# charging_booster.net
KiCad netlist of a schematic drawn in Altium Designer
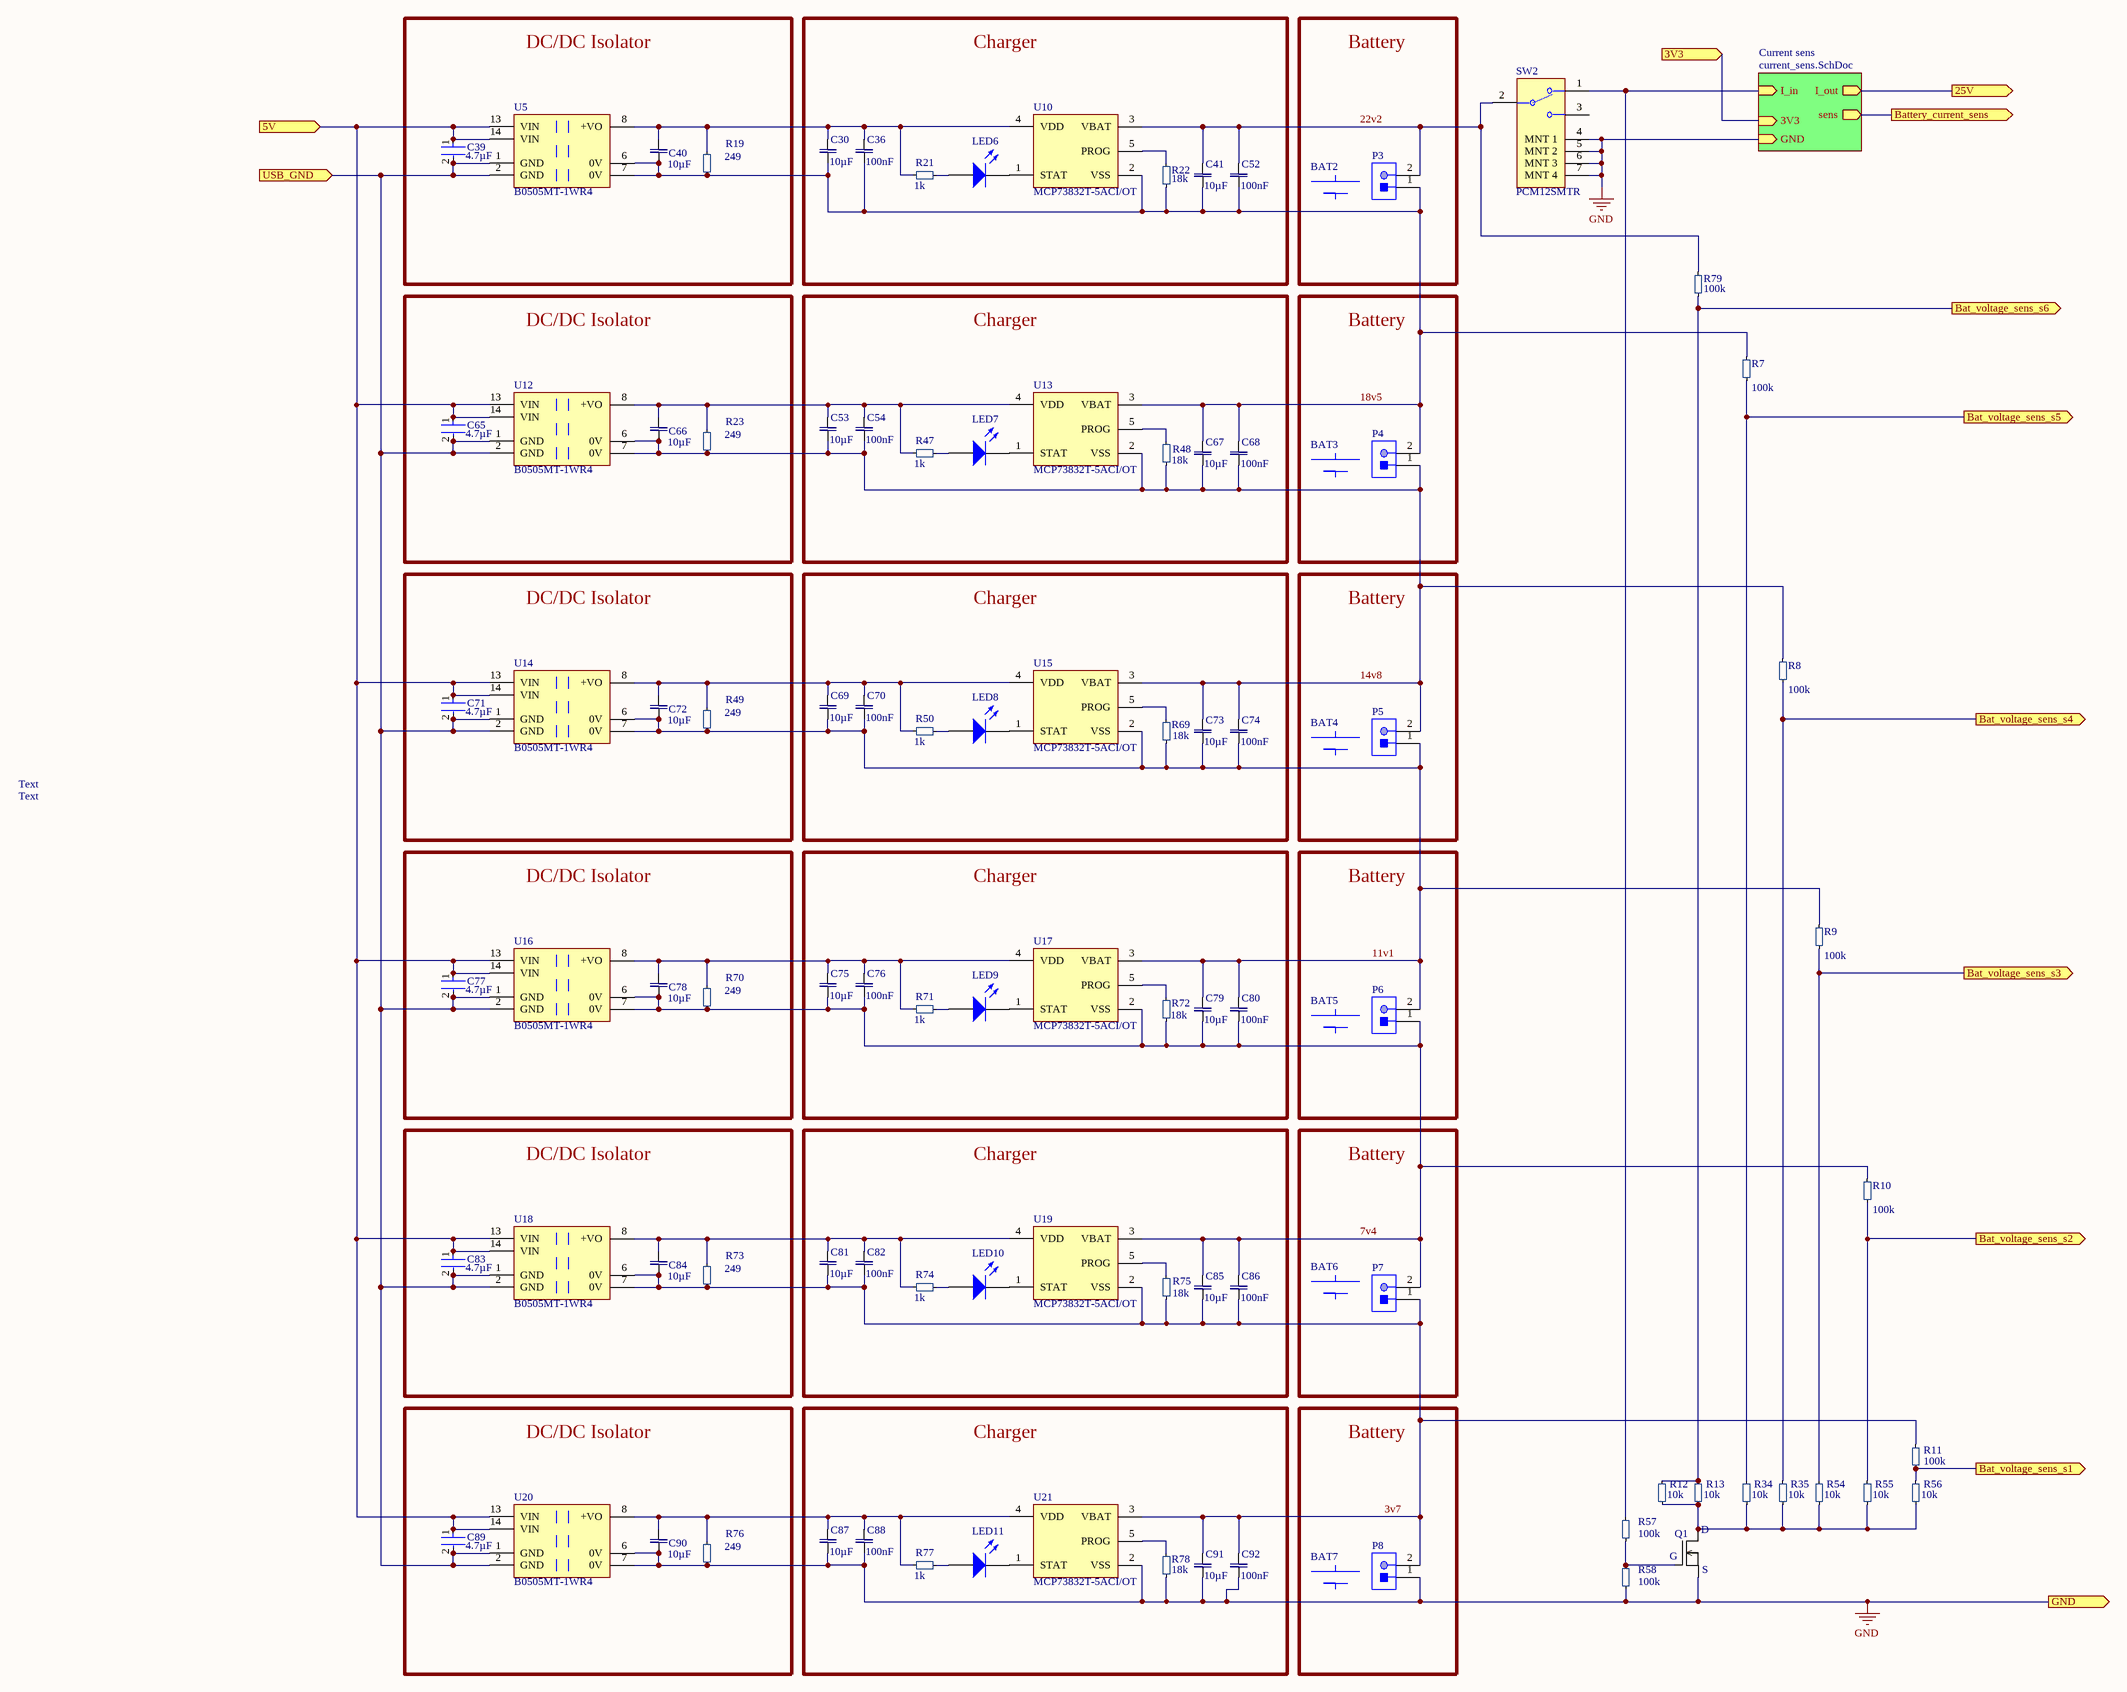
[diagram p0: charging_booster.SchDoc]

(export (version "E")
  (design (tool "Eeschema 10.0.6"))
  (components
    (comp (ref "BAT2")
      (value "702035_380mAH_20C_ebay")
      (description "https://www.ebay.com/itm/122071978357")
      (fields (field (name "VOLTAGE") "3.7V"))
      (libsource (lib "concord server") (part "606090_4000mAH_ebay"))
    )
    (comp (ref "BAT3")
      (value "702035_380mAH_20C_ebay")
      (description "https://www.ebay.com/itm/122071978357")
      (fields (field (name "VOLTAGE") "3.7V"))
      (libsource (lib "concord server") (part "606090_4000mAH_ebay"))
    )
    (comp (ref "BAT4")
      (value "702035_380mAH_20C_ebay")
      (description "https://www.ebay.com/itm/122071978357")
      (fields (field (name "VOLTAGE") "3.7V"))
      (libsource (lib "concord server") (part "606090_4000mAH_ebay"))
    )
    (comp (ref "BAT5")
      (value "702035_380mAH_20C_ebay")
      (description "https://www.ebay.com/itm/122071978357")
      (fields (field (name "VOLTAGE") "3.7V"))
      (libsource (lib "concord server") (part "606090_4000mAH_ebay"))
    )
    (comp (ref "BAT6")
      (value "702035_380mAH_20C_ebay")
      (description "https://www.ebay.com/itm/122071978357")
      (fields (field (name "VOLTAGE") "3.7V"))
      (libsource (lib "concord server") (part "606090_4000mAH_ebay"))
    )
    (comp (ref "BAT7")
      (value "702035_380mAH_20C_ebay")
      (description "https://www.ebay.com/itm/122071978357")
      (fields (field (name "VOLTAGE") "3.7V"))
      (libsource (lib "concord server") (part "606090_4000mAH_ebay"))
    )
    (comp (ref "C30")
      (value "CL31A106MBHNNNE")
      (footprint "Chip2PinSM127P600-8N")
      (description "CAP CER 10UF 50V X5R 1206")
      (fields (field (name "CAPACITANCE") "10µF") (field (name "TOLERANCE") "20%"))
      (libsource (lib "concord server") (part "Capasitor_keramic_generic"))
    )
    (comp (ref "C36")
      (value "GRM155R71H104ME14D")
      (footprint "cap0402")
      (description "0402 0.1 uF 50 V ±20% Tolerance X7R SMT Monolithic Ceramic Chip Capacitor")
      (fields (field (name "CAPACITANCE") "100nF") (field (name "TOLERANCE") "20%"))
      (libsource (lib "concord server") (part "Capasitor_keramic_generic"))
    )
    (comp (ref "C39")
      (value "CL21A475KAQNNNE")
      (footprint "FP-CL21-IPC_A")
      (fields (field (name "CAPACITANCE") "4.7µF") (field (name "TOLERANCE") "10%"))
      (libsource (lib "concord server") (part "b4654b650e69147ec39a6b967a45e02"))
    )
    (comp (ref "C40")
      (value "CL31A106MBHNNNE")
      (footprint "Chip2PinSM127P600-8N")
      (description "CAP CER 10UF 50V X5R 1206")
      (fields (field (name "CAPACITANCE") "10µF") (field (name "TOLERANCE") "20%"))
      (libsource (lib "concord server") (part "Capasitor_keramic_generic"))
    )
    (comp (ref "C41")
      (value "CL31A106MBHNNNE")
      (footprint "Chip2PinSM127P600-8N")
      (description "CAP CER 10UF 50V X5R 1206")
      (fields (field (name "CAPACITANCE") "10µF") (field (name "TOLERANCE") "20%"))
      (libsource (lib "concord server") (part "Capasitor_keramic_generic"))
    )
    (comp (ref "C52")
      (value "GRM155R71H104ME14D")
      (footprint "cap0402")
      (description "0402 0.1 uF 50 V ±20% Tolerance X7R SMT Monolithic Ceramic Chip Capacitor")
      (fields (field (name "CAPACITANCE") "100nF") (field (name "TOLERANCE") "20%"))
      (libsource (lib "concord server") (part "Capasitor_keramic_generic"))
    )
    (comp (ref "C53")
      (value "CL31A106MBHNNNE")
      (footprint "Chip2PinSM127P600-8N")
      (description "CAP CER 10UF 50V X5R 1206")
      (fields (field (name "CAPACITANCE") "10µF") (field (name "TOLERANCE") "20%"))
      (libsource (lib "concord server") (part "Capasitor_keramic_generic"))
    )
    (comp (ref "C54")
      (value "GRM155R71H104ME14D")
      (footprint "cap0402")
      (description "0402 0.1 uF 50 V ±20% Tolerance X7R SMT Monolithic Ceramic Chip Capacitor")
      (fields (field (name "CAPACITANCE") "100nF") (field (name "TOLERANCE") "20%"))
      (libsource (lib "concord server") (part "Capasitor_keramic_generic"))
    )
    (comp (ref "C65")
      (value "CL21A475KAQNNNE")
      (footprint "FP-CL21-IPC_A")
      (fields (field (name "CAPACITANCE") "4.7µF") (field (name "TOLERANCE") "10%"))
      (libsource (lib "concord server") (part "b4654b650e69147ec39a6b967a45e02"))
    )
    (comp (ref "C66")
      (value "CL31A106MBHNNNE")
      (footprint "Chip2PinSM127P600-8N")
      (description "CAP CER 10UF 50V X5R 1206")
      (fields (field (name "CAPACITANCE") "10µF") (field (name "TOLERANCE") "20%"))
      (libsource (lib "concord server") (part "Capasitor_keramic_generic"))
    )
    (comp (ref "C67")
      (value "CL31A106MBHNNNE")
      (footprint "Chip2PinSM127P600-8N")
      (description "CAP CER 10UF 50V X5R 1206")
      (fields (field (name "CAPACITANCE") "10µF") (field (name "TOLERANCE") "20%"))
      (libsource (lib "concord server") (part "Capasitor_keramic_generic"))
    )
    (comp (ref "C68")
      (value "GRM155R71H104ME14D")
      (footprint "cap0402")
      (description "0402 0.1 uF 50 V ±20% Tolerance X7R SMT Monolithic Ceramic Chip Capacitor")
      (fields (field (name "CAPACITANCE") "100nF") (field (name "TOLERANCE") "20%"))
      (libsource (lib "concord server") (part "Capasitor_keramic_generic"))
    )
    (comp (ref "C69")
      (value "CL31A106MBHNNNE")
      (footprint "Chip2PinSM127P600-8N")
      (description "CAP CER 10UF 50V X5R 1206")
      (fields (field (name "CAPACITANCE") "10µF") (field (name "TOLERANCE") "20%"))
      (libsource (lib "concord server") (part "Capasitor_keramic_generic"))
    )
    (comp (ref "C70")
      (value "GRM155R71H104ME14D")
      (footprint "cap0402")
      (description "0402 0.1 uF 50 V ±20% Tolerance X7R SMT Monolithic Ceramic Chip Capacitor")
      (fields (field (name "CAPACITANCE") "100nF") (field (name "TOLERANCE") "20%"))
      (libsource (lib "concord server") (part "Capasitor_keramic_generic"))
    )
    (comp (ref "C71")
      (value "CL21A475KAQNNNE")
      (footprint "FP-CL21-IPC_A")
      (fields (field (name "CAPACITANCE") "4.7µF") (field (name "TOLERANCE") "10%"))
      (libsource (lib "concord server") (part "b4654b650e69147ec39a6b967a45e02"))
    )
    (comp (ref "C72")
      (value "CL31A106MBHNNNE")
      (footprint "Chip2PinSM127P600-8N")
      (description "CAP CER 10UF 50V X5R 1206")
      (fields (field (name "CAPACITANCE") "10µF") (field (name "TOLERANCE") "20%"))
      (libsource (lib "concord server") (part "Capasitor_keramic_generic"))
    )
    (comp (ref "C73")
      (value "CL31A106MBHNNNE")
      (footprint "Chip2PinSM127P600-8N")
      (description "CAP CER 10UF 50V X5R 1206")
      (fields (field (name "CAPACITANCE") "10µF") (field (name "TOLERANCE") "20%"))
      (libsource (lib "concord server") (part "Capasitor_keramic_generic"))
    )
    (comp (ref "C74")
      (value "GRM155R71H104ME14D")
      (footprint "cap0402")
      (description "0402 0.1 uF 50 V ±20% Tolerance X7R SMT Monolithic Ceramic Chip Capacitor")
      (fields (field (name "CAPACITANCE") "100nF") (field (name "TOLERANCE") "20%"))
      (libsource (lib "concord server") (part "Capasitor_keramic_generic"))
    )
    (comp (ref "C75")
      (value "CL31A106MBHNNNE")
      (footprint "Chip2PinSM127P600-8N")
      (description "CAP CER 10UF 50V X5R 1206")
      (fields (field (name "CAPACITANCE") "10µF") (field (name "TOLERANCE") "20%"))
      (libsource (lib "concord server") (part "Capasitor_keramic_generic"))
    )
    (comp (ref "C76")
      (value "GRM155R71H104ME14D")
      (footprint "cap0402")
      (description "0402 0.1 uF 50 V ±20% Tolerance X7R SMT Monolithic Ceramic Chip Capacitor")
      (fields (field (name "CAPACITANCE") "100nF") (field (name "TOLERANCE") "20%"))
      (libsource (lib "concord server") (part "Capasitor_keramic_generic"))
    )
    (comp (ref "C77")
      (value "CL21A475KAQNNNE")
      (footprint "FP-CL21-IPC_A")
      (fields (field (name "CAPACITANCE") "4.7µF") (field (name "TOLERANCE") "10%"))
      (libsource (lib "concord server") (part "b4654b650e69147ec39a6b967a45e02"))
    )
    (comp (ref "C78")
      (value "CL31A106MBHNNNE")
      (footprint "Chip2PinSM127P600-8N")
      (description "CAP CER 10UF 50V X5R 1206")
      (fields (field (name "CAPACITANCE") "10µF") (field (name "TOLERANCE") "20%"))
      (libsource (lib "concord server") (part "Capasitor_keramic_generic"))
    )
    (comp (ref "C79")
      (value "CL31A106MBHNNNE")
      (footprint "Chip2PinSM127P600-8N")
      (description "CAP CER 10UF 50V X5R 1206")
      (fields (field (name "CAPACITANCE") "10µF") (field (name "TOLERANCE") "20%"))
      (libsource (lib "concord server") (part "Capasitor_keramic_generic"))
    )
    (comp (ref "C80")
      (value "GRM155R71H104ME14D")
      (footprint "cap0402")
      (description "0402 0.1 uF 50 V ±20% Tolerance X7R SMT Monolithic Ceramic Chip Capacitor")
      (fields (field (name "CAPACITANCE") "100nF") (field (name "TOLERANCE") "20%"))
      (libsource (lib "concord server") (part "Capasitor_keramic_generic"))
    )
    (comp (ref "C81")
      (value "CL31A106MBHNNNE")
      (footprint "Chip2PinSM127P600-8N")
      (description "CAP CER 10UF 50V X5R 1206")
      (fields (field (name "CAPACITANCE") "10µF") (field (name "TOLERANCE") "20%"))
      (libsource (lib "concord server") (part "Capasitor_keramic_generic"))
    )
    (comp (ref "C82")
      (value "GRM155R71H104ME14D")
      (footprint "cap0402")
      (description "0402 0.1 uF 50 V ±20% Tolerance X7R SMT Monolithic Ceramic Chip Capacitor")
      (fields (field (name "CAPACITANCE") "100nF") (field (name "TOLERANCE") "20%"))
      (libsource (lib "concord server") (part "Capasitor_keramic_generic"))
    )
    (comp (ref "C83")
      (value "CL21A475KAQNNNE")
      (footprint "FP-CL21-IPC_A")
      (fields (field (name "CAPACITANCE") "4.7µF") (field (name "TOLERANCE") "10%"))
      (libsource (lib "concord server") (part "b4654b650e69147ec39a6b967a45e02"))
    )
    (comp (ref "C84")
      (value "CL31A106MBHNNNE")
      (footprint "Chip2PinSM127P600-8N")
      (description "CAP CER 10UF 50V X5R 1206")
      (fields (field (name "CAPACITANCE") "10µF") (field (name "TOLERANCE") "20%"))
      (libsource (lib "concord server") (part "Capasitor_keramic_generic"))
    )
    (comp (ref "C85")
      (value "CL31A106MBHNNNE")
      (footprint "Chip2PinSM127P600-8N")
      (description "CAP CER 10UF 50V X5R 1206")
      (fields (field (name "CAPACITANCE") "10µF") (field (name "TOLERANCE") "20%"))
      (libsource (lib "concord server") (part "Capasitor_keramic_generic"))
    )
    (comp (ref "C86")
      (value "GRM155R71H104ME14D")
      (footprint "cap0402")
      (description "0402 0.1 uF 50 V ±20% Tolerance X7R SMT Monolithic Ceramic Chip Capacitor")
      (fields (field (name "CAPACITANCE") "100nF") (field (name "TOLERANCE") "20%"))
      (libsource (lib "concord server") (part "Capasitor_keramic_generic"))
    )
    (comp (ref "C87")
      (value "CL31A106MBHNNNE")
      (footprint "Chip2PinSM127P600-8N")
      (description "CAP CER 10UF 50V X5R 1206")
      (fields (field (name "CAPACITANCE") "10µF") (field (name "TOLERANCE") "20%"))
      (libsource (lib "concord server") (part "Capasitor_keramic_generic"))
    )
    (comp (ref "C88")
      (value "GRM155R71H104ME14D")
      (footprint "cap0402")
      (description "0402 0.1 uF 50 V ±20% Tolerance X7R SMT Monolithic Ceramic Chip Capacitor")
      (fields (field (name "CAPACITANCE") "100nF") (field (name "TOLERANCE") "20%"))
      (libsource (lib "concord server") (part "Capasitor_keramic_generic"))
    )
    (comp (ref "C89")
      (value "CL21A475KAQNNNE")
      (footprint "FP-CL21-IPC_A")
      (fields (field (name "CAPACITANCE") "4.7µF") (field (name "TOLERANCE") "10%"))
      (libsource (lib "concord server") (part "b4654b650e69147ec39a6b967a45e02"))
    )
    (comp (ref "C90")
      (value "CL31A106MBHNNNE")
      (footprint "Chip2PinSM127P600-8N")
      (description "CAP CER 10UF 50V X5R 1206")
      (fields (field (name "CAPACITANCE") "10µF") (field (name "TOLERANCE") "20%"))
      (libsource (lib "concord server") (part "Capasitor_keramic_generic"))
    )
    (comp (ref "C91")
      (value "CL31A106MBHNNNE")
      (footprint "Chip2PinSM127P600-8N")
      (description "CAP CER 10UF 50V X5R 1206")
      (fields (field (name "CAPACITANCE") "10µF") (field (name "TOLERANCE") "20%"))
      (libsource (lib "concord server") (part "Capasitor_keramic_generic"))
    )
    (comp (ref "C92")
      (value "GRM155R71H104ME14D")
      (footprint "cap0402")
      (description "0402 0.1 uF 50 V ±20% Tolerance X7R SMT Monolithic Ceramic Chip Capacitor")
      (fields (field (name "CAPACITANCE") "100nF") (field (name "TOLERANCE") "20%"))
      (libsource (lib "concord server") (part "Capasitor_keramic_generic"))
    )
    (comp (ref "LED6")
      (value "150080BS75000")
      (footprint "0805_A")
      (description "SMD LED blue 3.5 V 0805, 150080BS75000, Würth Elektronik")
      (libsource (lib "concord server") (part "WE-LED_K1A2-2"))
    )
    (comp (ref "LED7")
      (value "150080BS75000")
      (footprint "0805_A")
      (description "SMD LED blue 3.5 V 0805, 150080BS75000, Würth Elektronik")
      (libsource (lib "concord server") (part "WE-LED_K1A2-2"))
    )
    (comp (ref "LED8")
      (value "150080BS75000")
      (footprint "0805_A")
      (description "SMD LED blue 3.5 V 0805, 150080BS75000, Würth Elektronik")
      (libsource (lib "concord server") (part "WE-LED_K1A2-2"))
    )
    (comp (ref "LED9")
      (value "150080BS75000")
      (footprint "0805_A")
      (description "SMD LED blue 3.5 V 0805, 150080BS75000, Würth Elektronik")
      (libsource (lib "concord server") (part "WE-LED_K1A2-2"))
    )
    (comp (ref "LED10")
      (value "150080BS75000")
      (footprint "0805_A")
      (description "SMD LED blue 3.5 V 0805, 150080BS75000, Würth Elektronik")
      (libsource (lib "concord server") (part "WE-LED_K1A2-2"))
    )
    (comp (ref "LED11")
      (value "150080BS75000")
      (footprint "0805_A")
      (description "SMD LED blue 3.5 V 0805, 150080BS75000, Würth Elektronik")
      (libsource (lib "concord server") (part "WE-LED_K1A2-2"))
    )
    (comp (ref "P3")
      (value "S2B-XH-A(LF)(SN)")
      (footprint "JST-S2B-XH-A(LF)(SN)_V")
      (description "XH Series 2.5mm 2 Position Through Hole Shrouded Header Connector")
      (libsource (lib "concord server") (part "CN-1P-M-R2"))
    )
    (comp (ref "P4")
      (value "S2B-XH-A(LF)(SN)")
      (footprint "JST-S2B-XH-A(LF)(SN)_V")
      (description "XH Series 2.5mm 2 Position Through Hole Shrouded Header Connector")
      (libsource (lib "concord server") (part "CN-1P-M-R2"))
    )
    (comp (ref "P5")
      (value "S2B-XH-A(LF)(SN)")
      (footprint "JST-S2B-XH-A(LF)(SN)_V")
      (description "XH Series 2.5mm 2 Position Through Hole Shrouded Header Connector")
      (libsource (lib "concord server") (part "CN-1P-M-R2"))
    )
    (comp (ref "P6")
      (value "S2B-XH-A(LF)(SN)")
      (footprint "JST-S2B-XH-A(LF)(SN)_V")
      (description "XH Series 2.5mm 2 Position Through Hole Shrouded Header Connector")
      (libsource (lib "concord server") (part "CN-1P-M-R2"))
    )
    (comp (ref "P7")
      (value "S2B-XH-A(LF)(SN)")
      (footprint "JST-S2B-XH-A(LF)(SN)_V")
      (description "XH Series 2.5mm 2 Position Through Hole Shrouded Header Connector")
      (libsource (lib "concord server") (part "CN-1P-M-R2"))
    )
    (comp (ref "P8")
      (value "S2B-XH-A(LF)(SN)")
      (footprint "JST-S2B-XH-A(LF)(SN)_V")
      (description "XH Series 2.5mm 2 Position Through Hole Shrouded Header Connector")
      (libsource (lib "concord server") (part "CN-1P-M-R2"))
    )
    (comp (ref "Q1")
      (value "SSM3K7002CFU,LF")
      (footprint "SSM3K7002CFU,LF-Footprint-1")
      (description "Trans MOSFET N-CH Si 60V 0.17A 3-Pin USM T/R")
      (libsource (lib "concord server") (part "nmos"))
    )
    (comp (ref "R7")
      (value "RC0402FR-07100KL")
      (footprint "SMD_0402(1005)_M")
      (description "Res General Purpose Thick Film 0402 100K Ohm 1% 1/16W ±100ppm/°C Molded SMD Paper T/R")
      (fields (field (name "RESISTANCE") "100k") (field (name "TOLERANCE") "1%"))
      (libsource (lib "concord server") (part "resistor_european"))
    )
    (comp (ref "R8")
      (value "RC0402FR-07100KL")
      (footprint "SMD_0402(1005)_M")
      (description "Res General Purpose Thick Film 0402 100K Ohm 1% 1/16W ±100ppm/°C Molded SMD Paper T/R")
      (fields (field (name "RESISTANCE") "100k") (field (name "TOLERANCE") "1%"))
      (libsource (lib "concord server") (part "resistor_european"))
    )
    (comp (ref "R9")
      (value "RC0402FR-07100KL")
      (footprint "SMD_0402(1005)_M")
      (description "Res General Purpose Thick Film 0402 100K Ohm 1% 1/16W ±100ppm/°C Molded SMD Paper T/R")
      (fields (field (name "RESISTANCE") "100k") (field (name "TOLERANCE") "1%"))
      (libsource (lib "concord server") (part "resistor_european"))
    )
    (comp (ref "R10")
      (value "RC0402FR-07100KL")
      (footprint "SMD_0402(1005)_M")
      (description "Res General Purpose Thick Film 0402 100K Ohm 1% 1/16W ±100ppm/°C Molded SMD Paper T/R")
      (fields (field (name "RESISTANCE") "100k") (field (name "TOLERANCE") "1%"))
      (libsource (lib "concord server") (part "resistor_european"))
    )
    (comp (ref "R11")
      (value "RC0402FR-07100KL")
      (footprint "SMD_0402(1005)_M")
      (description "Res General Purpose Thick Film 0402 100K Ohm 1% 1/16W ±100ppm/°C Molded SMD Paper T/R")
      (fields (field (name "RESISTANCE") "100k") (field (name "TOLERANCE") "1%"))
      (libsource (lib "concord server") (part "resistor_european"))
    )
    (comp (ref "R12")
      (value "RC0402FR-0710KL")
      (footprint "SMD_0402(1005)_M")
      (description "Surface Mount Thick Film Resistor, Rc Series, 10 Kohm, 62.5 Mw, - 1%, 50 V, 0402 [1005 Metric]")
      (fields (field (name "RESISTANCE") "10k") (field (name "TOLERANCE") "1%"))
      (libsource (lib "concord server") (part "resistor_european"))
    )
    (comp (ref "R13")
      (value "RC0402FR-0710KL")
      (footprint "SMD_0402(1005)_M")
      (description "Surface Mount Thick Film Resistor, Rc Series, 10 Kohm, 62.5 Mw, - 1%, 50 V, 0402 [1005 Metric]")
      (fields (field (name "RESISTANCE") "10k") (field (name "TOLERANCE") "1%"))
      (libsource (lib "concord server") (part "resistor_european"))
    )
    (comp (ref "R19")
      (value "RC0402FR-07249RL")
      (footprint "SMD_0402(1005)_M")
      (description "Res Thick Film 0402 249 Ohm 1% 1/16W ±100ppm/°C Molded SMD Paper T/R")
      (fields (field (name "RESISTANCE") "249") (field (name "TOLERANCE") "1%"))
      (libsource (lib "concord server") (part "resistor_european"))
    )
    (comp (ref "R21")
      (value "RC0402FR-071KL")
      (footprint "SMD_0402(1005)_M")
      (description "Surface Mount Chip Resistor, Thick Film, RC Series, 1 kohm, 62.5 mW, 1%, 50 V, 0402 [1005 Metric]")
      (fields (field (name "RESISTANCE") "1k") (field (name "TOLERANCE") "1%"))
      (libsource (lib "concord server") (part "resistor_european"))
    )
    (comp (ref "R22")
      (value "RC0402FR0718K")
      (footprint "RESC1005X40X25NL05T10")
      (description "RES SMD 18K OHM 1% 1/16W 0402")
      (fields (field (name "RESISTANCE") "18k") (field (name "TOLERANCE") "1%"))
      (libsource (lib "concord server") (part "resistor_european"))
    )
    (comp (ref "R23")
      (value "RC0402FR-07249RL")
      (footprint "SMD_0402(1005)_M")
      (description "Res Thick Film 0402 249 Ohm 1% 1/16W ±100ppm/°C Molded SMD Paper T/R")
      (fields (field (name "RESISTANCE") "249") (field (name "TOLERANCE") "1%"))
      (libsource (lib "concord server") (part "resistor_european"))
    )
    (comp (ref "R34")
      (value "RC0402FR-0710KL")
      (footprint "SMD_0402(1005)_M")
      (description "Surface Mount Thick Film Resistor, Rc Series, 10 Kohm, 62.5 Mw, - 1%, 50 V, 0402 [1005 Metric]")
      (fields (field (name "RESISTANCE") "10k") (field (name "TOLERANCE") "1%"))
      (libsource (lib "concord server") (part "resistor_european"))
    )
    (comp (ref "R35")
      (value "RC0402FR-0710KL")
      (footprint "SMD_0402(1005)_M")
      (description "Surface Mount Thick Film Resistor, Rc Series, 10 Kohm, 62.5 Mw, - 1%, 50 V, 0402 [1005 Metric]")
      (fields (field (name "RESISTANCE") "10k") (field (name "TOLERANCE") "1%"))
      (libsource (lib "concord server") (part "resistor_european"))
    )
    (comp (ref "R47")
      (value "RC0402FR-071KL")
      (footprint "SMD_0402(1005)_M")
      (description "Surface Mount Chip Resistor, Thick Film, RC Series, 1 kohm, 62.5 mW, 1%, 50 V, 0402 [1005 Metric]")
      (fields (field (name "RESISTANCE") "1k") (field (name "TOLERANCE") "1%"))
      (libsource (lib "concord server") (part "resistor_european"))
    )
    (comp (ref "R48")
      (value "RC0402FR0718K")
      (footprint "RESC1005X40X25NL05T10")
      (description "RES SMD 18K OHM 1% 1/16W 0402")
      (fields (field (name "RESISTANCE") "18k") (field (name "TOLERANCE") "1%"))
      (libsource (lib "concord server") (part "resistor_european"))
    )
    (comp (ref "R49")
      (value "RC0402FR-07249RL")
      (footprint "SMD_0402(1005)_M")
      (description "Res Thick Film 0402 249 Ohm 1% 1/16W ±100ppm/°C Molded SMD Paper T/R")
      (fields (field (name "RESISTANCE") "249") (field (name "TOLERANCE") "1%"))
      (libsource (lib "concord server") (part "resistor_european"))
    )
    (comp (ref "R50")
      (value "RC0402FR-071KL")
      (footprint "SMD_0402(1005)_M")
      (description "Surface Mount Chip Resistor, Thick Film, RC Series, 1 kohm, 62.5 mW, 1%, 50 V, 0402 [1005 Metric]")
      (fields (field (name "RESISTANCE") "1k") (field (name "TOLERANCE") "1%"))
      (libsource (lib "concord server") (part "resistor_european"))
    )
    (comp (ref "R54")
      (value "RC0402FR-0710KL")
      (footprint "SMD_0402(1005)_M")
      (description "Surface Mount Thick Film Resistor, Rc Series, 10 Kohm, 62.5 Mw, - 1%, 50 V, 0402 [1005 Metric]")
      (fields (field (name "RESISTANCE") "10k") (field (name "TOLERANCE") "1%"))
      (libsource (lib "concord server") (part "resistor_european"))
    )
    (comp (ref "R55")
      (value "RC0402FR-0710KL")
      (footprint "SMD_0402(1005)_M")
      (description "Surface Mount Thick Film Resistor, Rc Series, 10 Kohm, 62.5 Mw, - 1%, 50 V, 0402 [1005 Metric]")
      (fields (field (name "RESISTANCE") "10k") (field (name "TOLERANCE") "1%"))
      (libsource (lib "concord server") (part "resistor_european"))
    )
    (comp (ref "R56")
      (value "RC0402FR-0710KL")
      (footprint "SMD_0402(1005)_M")
      (description "Surface Mount Thick Film Resistor, Rc Series, 10 Kohm, 62.5 Mw, - 1%, 50 V, 0402 [1005 Metric]")
      (fields (field (name "RESISTANCE") "10k") (field (name "TOLERANCE") "1%"))
      (libsource (lib "concord server") (part "resistor_european"))
    )
    (comp (ref "R57")
      (value "RC0402FR-07100KL")
      (footprint "SMD_0402(1005)_M")
      (description "Res General Purpose Thick Film 0402 100K Ohm 1% 1/16W ±100ppm/°C Molded SMD Paper T/R")
      (fields (field (name "RESISTANCE") "100k") (field (name "TOLERANCE") "1%"))
      (libsource (lib "concord server") (part "resistor_european"))
    )
    (comp (ref "R58")
      (value "RC0402FR-07100KL")
      (footprint "SMD_0402(1005)_M")
      (description "Res General Purpose Thick Film 0402 100K Ohm 1% 1/16W ±100ppm/°C Molded SMD Paper T/R")
      (fields (field (name "RESISTANCE") "100k") (field (name "TOLERANCE") "1%"))
      (libsource (lib "concord server") (part "resistor_european"))
    )
    (comp (ref "R69")
      (value "RC0402FR0718K")
      (footprint "RESC1005X40X25NL05T10")
      (description "RES SMD 18K OHM 1% 1/16W 0402")
      (fields (field (name "RESISTANCE") "18k") (field (name "TOLERANCE") "1%"))
      (libsource (lib "concord server") (part "resistor_european"))
    )
    (comp (ref "R70")
      (value "RC0402FR-07249RL")
      (footprint "SMD_0402(1005)_M")
      (description "Res Thick Film 0402 249 Ohm 1% 1/16W ±100ppm/°C Molded SMD Paper T/R")
      (fields (field (name "RESISTANCE") "249") (field (name "TOLERANCE") "1%"))
      (libsource (lib "concord server") (part "resistor_european"))
    )
    (comp (ref "R71")
      (value "RC0402FR-071KL")
      (footprint "SMD_0402(1005)_M")
      (description "Surface Mount Chip Resistor, Thick Film, RC Series, 1 kohm, 62.5 mW, 1%, 50 V, 0402 [1005 Metric]")
      (fields (field (name "RESISTANCE") "1k") (field (name "TOLERANCE") "1%"))
      (libsource (lib "concord server") (part "resistor_european"))
    )
    (comp (ref "R72")
      (value "RC0402FR0718K")
      (footprint "RESC1005X40X25NL05T10")
      (description "RES SMD 18K OHM 1% 1/16W 0402")
      (fields (field (name "RESISTANCE") "18k") (field (name "TOLERANCE") "1%"))
      (libsource (lib "concord server") (part "resistor_european"))
    )
    (comp (ref "R73")
      (value "RC0402FR-07249RL")
      (footprint "SMD_0402(1005)_M")
      (description "Res Thick Film 0402 249 Ohm 1% 1/16W ±100ppm/°C Molded SMD Paper T/R")
      (fields (field (name "RESISTANCE") "249") (field (name "TOLERANCE") "1%"))
      (libsource (lib "concord server") (part "resistor_european"))
    )
    (comp (ref "R74")
      (value "RC0402FR-071KL")
      (footprint "SMD_0402(1005)_M")
      (description "Surface Mount Chip Resistor, Thick Film, RC Series, 1 kohm, 62.5 mW, 1%, 50 V, 0402 [1005 Metric]")
      (fields (field (name "RESISTANCE") "1k") (field (name "TOLERANCE") "1%"))
      (libsource (lib "concord server") (part "resistor_european"))
    )
    (comp (ref "R75")
      (value "RC0402FR0718K")
      (footprint "RESC1005X40X25NL05T10")
      (description "RES SMD 18K OHM 1% 1/16W 0402")
      (fields (field (name "RESISTANCE") "18k") (field (name "TOLERANCE") "1%"))
      (libsource (lib "concord server") (part "resistor_european"))
    )
    (comp (ref "R76")
      (value "RC0402FR-07249RL")
      (footprint "SMD_0402(1005)_M")
      (description "Res Thick Film 0402 249 Ohm 1% 1/16W ±100ppm/°C Molded SMD Paper T/R")
      (fields (field (name "RESISTANCE") "249") (field (name "TOLERANCE") "1%"))
      (libsource (lib "concord server") (part "resistor_european"))
    )
    (comp (ref "R77")
      (value "RC0402FR-071KL")
      (footprint "SMD_0402(1005)_M")
      (description "Surface Mount Chip Resistor, Thick Film, RC Series, 1 kohm, 62.5 mW, 1%, 50 V, 0402 [1005 Metric]")
      (fields (field (name "RESISTANCE") "1k") (field (name "TOLERANCE") "1%"))
      (libsource (lib "concord server") (part "resistor_european"))
    )
    (comp (ref "R78")
      (value "RC0402FR0718K")
      (footprint "RESC1005X40X25NL05T10")
      (description "RES SMD 18K OHM 1% 1/16W 0402")
      (fields (field (name "RESISTANCE") "18k") (field (name "TOLERANCE") "1%"))
      (libsource (lib "concord server") (part "resistor_european"))
    )
    (comp (ref "R79")
      (value "RC0402FR-07100KL")
      (footprint "SMD_0402(1005)_M")
      (description "Res General Purpose Thick Film 0402 100K Ohm 1% 1/16W ±100ppm/°C Molded SMD Paper T/R")
      (fields (field (name "RESISTANCE") "100k") (field (name "TOLERANCE") "1%"))
      (libsource (lib "concord server") (part "resistor_european"))
    )
    (comp (ref "SW2")
      (value "PCM12SMTR")
      (footprint "FP-PCM12SMTR-MFG")
      (description "C & K COMPONENTS - PCM12SMTR - SWITCH, SPDT, 0.3A, 6VDC, SMD")
      (libsource (lib "concord server") (part "1a3f67d7e2b5469b171eeab59ffb4d2"))
    )
    (comp (ref "U5")
      (value "B0505MT-1WR4")
      (footprint "FP-B0505MT-1WR4-MFG")
      (description "DC DC Converter 5V 1W")
      (libsource (lib "concord server") (part "6a7141d3c8d3c77bdd270da68c65698"))
    )
    (comp (ref "U10")
      (value "MCP73832T-5ACI/OT")
      (footprint "SOT-23-OT5_M")
      (libsource (lib "concord server") (part "PM-BM-MCP73832-SOT5"))
    )
    (comp (ref "U12")
      (value "B0505MT-1WR4")
      (footprint "FP-B0505MT-1WR4-MFG")
      (description "DC DC Converter 5V 1W")
      (libsource (lib "concord server") (part "6a7141d3c8d3c77bdd270da68c65698"))
    )
    (comp (ref "U13")
      (value "MCP73832T-5ACI/OT")
      (footprint "SOT-23-OT5_M")
      (libsource (lib "concord server") (part "PM-BM-MCP73832-SOT5"))
    )
    (comp (ref "U14")
      (value "B0505MT-1WR4")
      (footprint "FP-B0505MT-1WR4-MFG")
      (description "DC DC Converter 5V 1W")
      (libsource (lib "concord server") (part "6a7141d3c8d3c77bdd270da68c65698"))
    )
    (comp (ref "U15")
      (value "MCP73832T-5ACI/OT")
      (footprint "SOT-23-OT5_M")
      (libsource (lib "concord server") (part "PM-BM-MCP73832-SOT5"))
    )
    (comp (ref "U16")
      (value "B0505MT-1WR4")
      (footprint "FP-B0505MT-1WR4-MFG")
      (description "DC DC Converter 5V 1W")
      (libsource (lib "concord server") (part "6a7141d3c8d3c77bdd270da68c65698"))
    )
    (comp (ref "U17")
      (value "MCP73832T-5ACI/OT")
      (footprint "SOT-23-OT5_M")
      (libsource (lib "concord server") (part "PM-BM-MCP73832-SOT5"))
    )
    (comp (ref "U18")
      (value "B0505MT-1WR4")
      (footprint "FP-B0505MT-1WR4-MFG")
      (description "DC DC Converter 5V 1W")
      (libsource (lib "concord server") (part "6a7141d3c8d3c77bdd270da68c65698"))
    )
    (comp (ref "U19")
      (value "MCP73832T-5ACI/OT")
      (footprint "SOT-23-OT5_M")
      (libsource (lib "concord server") (part "PM-BM-MCP73832-SOT5"))
    )
    (comp (ref "U20")
      (value "B0505MT-1WR4")
      (footprint "FP-B0505MT-1WR4-MFG")
      (description "DC DC Converter 5V 1W")
      (libsource (lib "concord server") (part "6a7141d3c8d3c77bdd270da68c65698"))
    )
    (comp (ref "U21")
      (value "MCP73832T-5ACI/OT")
      (footprint "SOT-23-OT5_M")
      (libsource (lib "concord server") (part "PM-BM-MCP73832-SOT5"))
    )
  )
  (nets
    (net (code "2") (name "/3v7") (class "Default")
      (node (ref "C81") (pin "1") (pinfunction "1_1") (pintype "passive"))
      (node (ref "C82") (pin "1") (pinfunction "1_1") (pintype "passive"))
      (node (ref "C84") (pin "1") (pinfunction "1_1") (pintype "passive"))
      (node (ref "C85") (pin "1") (pinfunction "1_1") (pintype "passive"))
      (node (ref "C86") (pin "1") (pinfunction "1_1") (pintype "passive"))
      (node (ref "C91") (pin "2") (pinfunction "2_2") (pintype "passive"))
      (node (ref "C92") (pin "2") (pinfunction "2_2") (pintype "passive"))
      (node (ref "P7") (pin "1") (pinfunction "1_1") (pintype "passive"))
      (node (ref "P8") (pin "2") (pinfunction "2_2") (pintype "passive"))
      (node (ref "R11") (pin "2") (pinfunction "2_2") (pintype "passive"))
      (node (ref "R73") (pin "1") (pinfunction "1_1") (pintype "passive"))
      (node (ref "R75") (pin "1") (pinfunction "1_1") (pintype "passive"))
      (node (ref "U18") (pin "6") (pinfunction "0V_6") (pintype "power_in"))
      (node (ref "U18") (pin "7") (pinfunction "0V_7") (pintype "power_in"))
      (node (ref "U19") (pin "2") (pinfunction "VSS_2") (pintype "power_in"))
      (node (ref "U21") (pin "3") (pinfunction "VBAT_3") (pintype "power_in"))
    )
    (net (code "3") (name "/5V") (class "Default")
      (node (ref "C39") (pin "1") (pinfunction "1_1") (pintype "passive"))
      (node (ref "C65") (pin "1") (pinfunction "1_1") (pintype "passive"))
      (node (ref "C71") (pin "1") (pinfunction "1_1") (pintype "passive"))
      (node (ref "C77") (pin "1") (pinfunction "1_1") (pintype "passive"))
      (node (ref "C83") (pin "1") (pinfunction "1_1") (pintype "passive"))
      (node (ref "C89") (pin "1") (pinfunction "1_1") (pintype "passive"))
      (node (ref "U12") (pin "13") (pinfunction "VIN_13") (pintype "power_in"))
      (node (ref "U12") (pin "14") (pinfunction "VIN_14") (pintype "power_in"))
      (node (ref "U14") (pin "13") (pinfunction "VIN_13") (pintype "power_in"))
      (node (ref "U14") (pin "14") (pinfunction "VIN_14") (pintype "power_in"))
      (node (ref "U16") (pin "13") (pinfunction "VIN_13") (pintype "power_in"))
      (node (ref "U16") (pin "14") (pinfunction "VIN_14") (pintype "power_in"))
      (node (ref "U18") (pin "13") (pinfunction "VIN_13") (pintype "power_in"))
      (node (ref "U18") (pin "14") (pinfunction "VIN_14") (pintype "power_in"))
      (node (ref "U20") (pin "13") (pinfunction "VIN_13") (pintype "power_in"))
      (node (ref "U20") (pin "14") (pinfunction "VIN_14") (pintype "power_in"))
      (node (ref "U5") (pin "13") (pinfunction "VIN_13") (pintype "power_in"))
      (node (ref "U5") (pin "14") (pinfunction "VIN_14") (pintype "power_in"))
    )
    (net (code "4") (name "/7v4") (class "Default")
      (node (ref "C75") (pin "1") (pinfunction "1_1") (pintype "passive"))
      (node (ref "C76") (pin "1") (pinfunction "1_1") (pintype "passive"))
      (node (ref "C78") (pin "1") (pinfunction "1_1") (pintype "passive"))
      (node (ref "C79") (pin "1") (pinfunction "1_1") (pintype "passive"))
      (node (ref "C80") (pin "1") (pinfunction "1_1") (pintype "passive"))
      (node (ref "C85") (pin "2") (pinfunction "2_2") (pintype "passive"))
      (node (ref "C86") (pin "2") (pinfunction "2_2") (pintype "passive"))
      (node (ref "P6") (pin "1") (pinfunction "1_1") (pintype "passive"))
      (node (ref "P7") (pin "2") (pinfunction "2_2") (pintype "passive"))
      (node (ref "R10") (pin "2") (pinfunction "2_2") (pintype "passive"))
      (node (ref "R70") (pin "1") (pinfunction "1_1") (pintype "passive"))
      (node (ref "R72") (pin "1") (pinfunction "1_1") (pintype "passive"))
      (node (ref "U16") (pin "6") (pinfunction "0V_6") (pintype "power_in"))
      (node (ref "U16") (pin "7") (pinfunction "0V_7") (pintype "power_in"))
      (node (ref "U17") (pin "2") (pinfunction "VSS_2") (pintype "power_in"))
      (node (ref "U19") (pin "3") (pinfunction "VBAT_3") (pintype "power_in"))
    )
    (net (code "5") (name "/11v1") (class "Default")
      (node (ref "C69") (pin "1") (pinfunction "1_1") (pintype "passive"))
      (node (ref "C70") (pin "1") (pinfunction "1_1") (pintype "passive"))
      (node (ref "C72") (pin "1") (pinfunction "1_1") (pintype "passive"))
      (node (ref "C73") (pin "1") (pinfunction "1_1") (pintype "passive"))
      (node (ref "C74") (pin "1") (pinfunction "1_1") (pintype "passive"))
      (node (ref "C79") (pin "2") (pinfunction "2_2") (pintype "passive"))
      (node (ref "C80") (pin "2") (pinfunction "2_2") (pintype "passive"))
      (node (ref "P5") (pin "1") (pinfunction "1_1") (pintype "passive"))
      (node (ref "P6") (pin "2") (pinfunction "2_2") (pintype "passive"))
      (node (ref "R49") (pin "1") (pinfunction "1_1") (pintype "passive"))
      (node (ref "R69") (pin "1") (pinfunction "1_1") (pintype "passive"))
      (node (ref "R9") (pin "2") (pinfunction "2_2") (pintype "passive"))
      (node (ref "U14") (pin "6") (pinfunction "0V_6") (pintype "power_in"))
      (node (ref "U14") (pin "7") (pinfunction "0V_7") (pintype "power_in"))
      (node (ref "U15") (pin "2") (pinfunction "VSS_2") (pintype "power_in"))
      (node (ref "U17") (pin "3") (pinfunction "VBAT_3") (pintype "power_in"))
    )
    (net (code "6") (name "/14v8") (class "Default")
      (node (ref "C53") (pin "1") (pinfunction "1_1") (pintype "passive"))
      (node (ref "C54") (pin "1") (pinfunction "1_1") (pintype "passive"))
      (node (ref "C66") (pin "1") (pinfunction "1_1") (pintype "passive"))
      (node (ref "C67") (pin "1") (pinfunction "1_1") (pintype "passive"))
      (node (ref "C68") (pin "1") (pinfunction "1_1") (pintype "passive"))
      (node (ref "C73") (pin "2") (pinfunction "2_2") (pintype "passive"))
      (node (ref "C74") (pin "2") (pinfunction "2_2") (pintype "passive"))
      (node (ref "P4") (pin "1") (pinfunction "1_1") (pintype "passive"))
      (node (ref "P5") (pin "2") (pinfunction "2_2") (pintype "passive"))
      (node (ref "R23") (pin "1") (pinfunction "1_1") (pintype "passive"))
      (node (ref "R48") (pin "1") (pinfunction "1_1") (pintype "passive"))
      (node (ref "R8") (pin "2") (pinfunction "2_2") (pintype "passive"))
      (node (ref "U12") (pin "6") (pinfunction "0V_6") (pintype "power_in"))
      (node (ref "U12") (pin "7") (pinfunction "0V_7") (pintype "power_in"))
      (node (ref "U13") (pin "2") (pinfunction "VSS_2") (pintype "power_in"))
      (node (ref "U15") (pin "3") (pinfunction "VBAT_3") (pintype "power_in"))
    )
    (net (code "7") (name "/18v5") (class "Default")
      (node (ref "C30") (pin "1") (pinfunction "1_1") (pintype "passive"))
      (node (ref "C36") (pin "1") (pinfunction "1_1") (pintype "passive"))
      (node (ref "C40") (pin "1") (pinfunction "1_1") (pintype "passive"))
      (node (ref "C41") (pin "1") (pinfunction "1_1") (pintype "passive"))
      (node (ref "C52") (pin "1") (pinfunction "1_1") (pintype "passive"))
      (node (ref "C67") (pin "2") (pinfunction "2_2") (pintype "passive"))
      (node (ref "C68") (pin "2") (pinfunction "2_2") (pintype "passive"))
      (node (ref "P3") (pin "1") (pinfunction "1_1") (pintype "passive"))
      (node (ref "P4") (pin "2") (pinfunction "2_2") (pintype "passive"))
      (node (ref "R19") (pin "1") (pinfunction "1_1") (pintype "passive"))
      (node (ref "R22") (pin "1") (pinfunction "1_1") (pintype "passive"))
      (node (ref "R7") (pin "2") (pinfunction "2_2") (pintype "passive"))
      (node (ref "U10") (pin "2") (pinfunction "VSS_2") (pintype "power_in"))
      (node (ref "U13") (pin "3") (pinfunction "VBAT_3") (pintype "power_in"))
      (node (ref "U5") (pin "6") (pinfunction "0V_6") (pintype "power_in"))
      (node (ref "U5") (pin "7") (pinfunction "0V_7") (pintype "power_in"))
    )
    (net (code "8") (name "/22v2") (class "Default")
      (node (ref "C41") (pin "2") (pinfunction "2_2") (pintype "passive"))
      (node (ref "C52") (pin "2") (pinfunction "2_2") (pintype "passive"))
      (node (ref "P3") (pin "2") (pinfunction "2_2") (pintype "passive"))
      (node (ref "R79") (pin "2") (pinfunction "2_2") (pintype "passive"))
      (node (ref "SW2") (pin "2") (pinfunction "2_2") (pintype "passive"))
      (node (ref "U10") (pin "3") (pinfunction "VBAT_3") (pintype "power_in"))
    )
    (net (code "10") (name "/Bat_voltage_sens_s1") (class "Default")
      (node (ref "R11") (pin "1") (pinfunction "1_1") (pintype "passive"))
      (node (ref "R56") (pin "2") (pinfunction "2_2") (pintype "passive"))
    )
    (net (code "11") (name "/Bat_voltage_sens_s2") (class "Default")
      (node (ref "R10") (pin "1") (pinfunction "1_1") (pintype "passive"))
      (node (ref "R55") (pin "2") (pinfunction "2_2") (pintype "passive"))
    )
    (net (code "12") (name "/Bat_voltage_sens_s3") (class "Default")
      (node (ref "R54") (pin "2") (pinfunction "2_2") (pintype "passive"))
      (node (ref "R9") (pin "1") (pinfunction "1_1") (pintype "passive"))
    )
    (net (code "13") (name "/Bat_voltage_sens_s4") (class "Default")
      (node (ref "R35") (pin "2") (pinfunction "2_2") (pintype "passive"))
      (node (ref "R8") (pin "1") (pinfunction "1_1") (pintype "passive"))
    )
    (net (code "14") (name "/Bat_voltage_sens_s5") (class "Default")
      (node (ref "R34") (pin "2") (pinfunction "2_2") (pintype "passive"))
      (node (ref "R7") (pin "1") (pinfunction "1_1") (pintype "passive"))
    )
    (net (code "15") (name "/Bat_voltage_sens_s6") (class "Default")
      (node (ref "R12") (pin "2") (pinfunction "2_2") (pintype "passive"))
      (node (ref "R13") (pin "2") (pinfunction "2_2") (pintype "passive"))
      (node (ref "R79") (pin "1") (pinfunction "1_1") (pintype "passive"))
    )
    (net (code "17") (name "/I_in") (class "Default")
      (node (ref "R57") (pin "2") (pinfunction "2_2") (pintype "passive"))
      (node (ref "SW2") (pin "1") (pinfunction "1_1") (pintype "passive"))
    )
    (net (code "18") (name "/USB_GND") (class "Default")
      (node (ref "C39") (pin "2") (pinfunction "2_2") (pintype "passive"))
      (node (ref "C65") (pin "2") (pinfunction "2_2") (pintype "passive"))
      (node (ref "C71") (pin "2") (pinfunction "2_2") (pintype "passive"))
      (node (ref "C77") (pin "2") (pinfunction "2_2") (pintype "passive"))
      (node (ref "C83") (pin "2") (pinfunction "2_2") (pintype "passive"))
      (node (ref "C89") (pin "2") (pinfunction "2_2") (pintype "passive"))
      (node (ref "U12") (pin "1") (pinfunction "GND_1") (pintype "power_in"))
      (node (ref "U12") (pin "2") (pinfunction "GND_2") (pintype "power_in"))
      (node (ref "U14") (pin "1") (pinfunction "GND_1") (pintype "power_in"))
      (node (ref "U14") (pin "2") (pinfunction "GND_2") (pintype "power_in"))
      (node (ref "U16") (pin "1") (pinfunction "GND_1") (pintype "power_in"))
      (node (ref "U16") (pin "2") (pinfunction "GND_2") (pintype "power_in"))
      (node (ref "U18") (pin "1") (pinfunction "GND_1") (pintype "power_in"))
      (node (ref "U18") (pin "2") (pinfunction "GND_2") (pintype "power_in"))
      (node (ref "U20") (pin "1") (pinfunction "GND_1") (pintype "power_in"))
      (node (ref "U20") (pin "2") (pinfunction "GND_2") (pintype "power_in"))
      (node (ref "U5") (pin "1") (pinfunction "GND_1") (pintype "power_in"))
      (node (ref "U5") (pin "2") (pinfunction "GND_2") (pintype "power_in"))
    )
    (net (code "19") (name "GND") (class "Default")
      (node (ref "C87") (pin "1") (pinfunction "1_1") (pintype "passive"))
      (node (ref "C88") (pin "1") (pinfunction "1_1") (pintype "passive"))
      (node (ref "C90") (pin "1") (pinfunction "1_1") (pintype "passive"))
      (node (ref "C91") (pin "1") (pinfunction "1_1") (pintype "passive"))
      (node (ref "C92") (pin "1") (pinfunction "1_1") (pintype "passive"))
      (node (ref "P8") (pin "1") (pinfunction "1_1") (pintype "passive"))
      (node (ref "Q1") (pin "2") (pinfunction "D_2") (pintype "passive"))
      (node (ref "R58") (pin "1") (pinfunction "1_1") (pintype "passive"))
      (node (ref "R76") (pin "1") (pinfunction "1_1") (pintype "passive"))
      (node (ref "R78") (pin "1") (pinfunction "1_1") (pintype "passive"))
      (node (ref "SW2") (pin "4") (pinfunction "MNT_1_4") (pintype "passive"))
      (node (ref "SW2") (pin "5") (pinfunction "MNT_2_5") (pintype "passive"))
      (node (ref "SW2") (pin "6") (pinfunction "MNT_3_6") (pintype "passive"))
      (node (ref "SW2") (pin "7") (pinfunction "MNT_4_7") (pintype "passive"))
      (node (ref "U20") (pin "6") (pinfunction "0V_6") (pintype "power_in"))
      (node (ref "U20") (pin "7") (pinfunction "0V_7") (pintype "power_in"))
      (node (ref "U21") (pin "2") (pinfunction "VSS_2") (pintype "power_in"))
    )
    (net (code "20") (name "Net-(LED6-A)") (class "Default")
      (node (ref "LED6") (pin "2") (pinfunction "A_2") (pintype "passive"))
      (node (ref "R21") (pin "1") (pinfunction "1_1") (pintype "passive"))
    )
    (net (code "21") (name "Net-(LED6-K)") (class "Default")
      (node (ref "LED6") (pin "1") (pinfunction "K_1") (pintype "passive"))
      (node (ref "U10") (pin "1") (pinfunction "STAT_1") (pintype "open_collector"))
    )
    (net (code "22") (name "Net-(LED7-A)") (class "Default")
      (node (ref "LED7") (pin "2") (pinfunction "A_2") (pintype "passive"))
      (node (ref "R47") (pin "1") (pinfunction "1_1") (pintype "passive"))
    )
    (net (code "23") (name "Net-(LED7-K)") (class "Default")
      (node (ref "LED7") (pin "1") (pinfunction "K_1") (pintype "passive"))
      (node (ref "U13") (pin "1") (pinfunction "STAT_1") (pintype "open_collector"))
    )
    (net (code "24") (name "Net-(LED8-A)") (class "Default")
      (node (ref "LED8") (pin "2") (pinfunction "A_2") (pintype "passive"))
      (node (ref "R50") (pin "1") (pinfunction "1_1") (pintype "passive"))
    )
    (net (code "25") (name "Net-(LED8-K)") (class "Default")
      (node (ref "LED8") (pin "1") (pinfunction "K_1") (pintype "passive"))
      (node (ref "U15") (pin "1") (pinfunction "STAT_1") (pintype "open_collector"))
    )
    (net (code "26") (name "Net-(LED9-A)") (class "Default")
      (node (ref "LED9") (pin "2") (pinfunction "A_2") (pintype "passive"))
      (node (ref "R71") (pin "1") (pinfunction "1_1") (pintype "passive"))
    )
    (net (code "27") (name "Net-(LED9-K)") (class "Default")
      (node (ref "LED9") (pin "1") (pinfunction "K_1") (pintype "passive"))
      (node (ref "U17") (pin "1") (pinfunction "STAT_1") (pintype "open_collector"))
    )
    (net (code "28") (name "Net-(LED10-A)") (class "Default")
      (node (ref "LED10") (pin "2") (pinfunction "A_2") (pintype "passive"))
      (node (ref "R74") (pin "1") (pinfunction "1_1") (pintype "passive"))
    )
    (net (code "29") (name "Net-(LED10-K)") (class "Default")
      (node (ref "LED10") (pin "1") (pinfunction "K_1") (pintype "passive"))
      (node (ref "U19") (pin "1") (pinfunction "STAT_1") (pintype "open_collector"))
    )
    (net (code "30") (name "Net-(LED11-A)") (class "Default")
      (node (ref "LED11") (pin "2") (pinfunction "A_2") (pintype "passive"))
      (node (ref "R77") (pin "1") (pinfunction "1_1") (pintype "passive"))
    )
    (net (code "31") (name "Net-(LED11-K)") (class "Default")
      (node (ref "LED11") (pin "1") (pinfunction "K_1") (pintype "passive"))
      (node (ref "U21") (pin "1") (pinfunction "STAT_1") (pintype "open_collector"))
    )
    (net (code "32") (name "Net-(Q1-G)") (class "Default")
      (node (ref "Q1") (pin "1") (pinfunction "G_1") (pintype "passive"))
      (node (ref "R57") (pin "1") (pinfunction "1_1") (pintype "passive"))
      (node (ref "R58") (pin "2") (pinfunction "2_2") (pintype "passive"))
    )
    (net (code "33") (name "Net-(Q1-S)") (class "Default")
      (node (ref "Q1") (pin "3") (pinfunction "S_3") (pintype "passive"))
      (node (ref "R12") (pin "1") (pinfunction "1_1") (pintype "passive"))
      (node (ref "R13") (pin "1") (pinfunction "1_1") (pintype "passive"))
      (node (ref "R34") (pin "1") (pinfunction "1_1") (pintype "passive"))
      (node (ref "R35") (pin "1") (pinfunction "1_1") (pintype "passive"))
      (node (ref "R54") (pin "1") (pinfunction "1_1") (pintype "passive"))
      (node (ref "R55") (pin "1") (pinfunction "1_1") (pintype "passive"))
      (node (ref "R56") (pin "1") (pinfunction "1_1") (pintype "passive"))
    )
    (net (code "34") (name "Net-(U10-PROG)") (class "Default")
      (node (ref "R22") (pin "2") (pinfunction "2_2") (pintype "passive"))
      (node (ref "U10") (pin "5") (pinfunction "PROG_5") (pintype "passive"))
    )
    (net (code "35") (name "Net-(U10-VDD)") (class "Default")
      (node (ref "C30") (pin "2") (pinfunction "2_2") (pintype "passive"))
      (node (ref "C36") (pin "2") (pinfunction "2_2") (pintype "passive"))
      (node (ref "C40") (pin "2") (pinfunction "2_2") (pintype "passive"))
      (node (ref "R19") (pin "2") (pinfunction "2_2") (pintype "passive"))
      (node (ref "R21") (pin "2") (pinfunction "2_2") (pintype "passive"))
      (node (ref "U10") (pin "4") (pinfunction "VDD_4") (pintype "power_in"))
      (node (ref "U5") (pin "8") (pinfunction "+VO_8") (pintype "power_in"))
    )
    (net (code "36") (name "Net-(U12-+VO)") (class "Default")
      (node (ref "C53") (pin "2") (pinfunction "2_2") (pintype "passive"))
      (node (ref "C54") (pin "2") (pinfunction "2_2") (pintype "passive"))
      (node (ref "C66") (pin "2") (pinfunction "2_2") (pintype "passive"))
      (node (ref "R23") (pin "2") (pinfunction "2_2") (pintype "passive"))
      (node (ref "R47") (pin "2") (pinfunction "2_2") (pintype "passive"))
      (node (ref "U12") (pin "8") (pinfunction "+VO_8") (pintype "power_in"))
      (node (ref "U13") (pin "4") (pinfunction "VDD_4") (pintype "power_in"))
    )
    (net (code "37") (name "Net-(U13-PROG)") (class "Default")
      (node (ref "R48") (pin "2") (pinfunction "2_2") (pintype "passive"))
      (node (ref "U13") (pin "5") (pinfunction "PROG_5") (pintype "passive"))
    )
    (net (code "38") (name "Net-(U14-+VO)") (class "Default")
      (node (ref "C69") (pin "2") (pinfunction "2_2") (pintype "passive"))
      (node (ref "C70") (pin "2") (pinfunction "2_2") (pintype "passive"))
      (node (ref "C72") (pin "2") (pinfunction "2_2") (pintype "passive"))
      (node (ref "R49") (pin "2") (pinfunction "2_2") (pintype "passive"))
      (node (ref "R50") (pin "2") (pinfunction "2_2") (pintype "passive"))
      (node (ref "U14") (pin "8") (pinfunction "+VO_8") (pintype "power_in"))
      (node (ref "U15") (pin "4") (pinfunction "VDD_4") (pintype "power_in"))
    )
    (net (code "39") (name "Net-(U15-PROG)") (class "Default")
      (node (ref "R69") (pin "2") (pinfunction "2_2") (pintype "passive"))
      (node (ref "U15") (pin "5") (pinfunction "PROG_5") (pintype "passive"))
    )
    (net (code "40") (name "Net-(U16-+VO)") (class "Default")
      (node (ref "C75") (pin "2") (pinfunction "2_2") (pintype "passive"))
      (node (ref "C76") (pin "2") (pinfunction "2_2") (pintype "passive"))
      (node (ref "C78") (pin "2") (pinfunction "2_2") (pintype "passive"))
      (node (ref "R70") (pin "2") (pinfunction "2_2") (pintype "passive"))
      (node (ref "R71") (pin "2") (pinfunction "2_2") (pintype "passive"))
      (node (ref "U16") (pin "8") (pinfunction "+VO_8") (pintype "power_in"))
      (node (ref "U17") (pin "4") (pinfunction "VDD_4") (pintype "power_in"))
    )
    (net (code "41") (name "Net-(U17-PROG)") (class "Default")
      (node (ref "R72") (pin "2") (pinfunction "2_2") (pintype "passive"))
      (node (ref "U17") (pin "5") (pinfunction "PROG_5") (pintype "passive"))
    )
    (net (code "42") (name "Net-(U18-+VO)") (class "Default")
      (node (ref "C81") (pin "2") (pinfunction "2_2") (pintype "passive"))
      (node (ref "C82") (pin "2") (pinfunction "2_2") (pintype "passive"))
      (node (ref "C84") (pin "2") (pinfunction "2_2") (pintype "passive"))
      (node (ref "R73") (pin "2") (pinfunction "2_2") (pintype "passive"))
      (node (ref "R74") (pin "2") (pinfunction "2_2") (pintype "passive"))
      (node (ref "U18") (pin "8") (pinfunction "+VO_8") (pintype "power_in"))
      (node (ref "U19") (pin "4") (pinfunction "VDD_4") (pintype "power_in"))
    )
    (net (code "43") (name "Net-(U19-PROG)") (class "Default")
      (node (ref "R75") (pin "2") (pinfunction "2_2") (pintype "passive"))
      (node (ref "U19") (pin "5") (pinfunction "PROG_5") (pintype "passive"))
    )
    (net (code "44") (name "Net-(U20-+VO)") (class "Default")
      (node (ref "C87") (pin "2") (pinfunction "2_2") (pintype "passive"))
      (node (ref "C88") (pin "2") (pinfunction "2_2") (pintype "passive"))
      (node (ref "C90") (pin "2") (pinfunction "2_2") (pintype "passive"))
      (node (ref "R76") (pin "2") (pinfunction "2_2") (pintype "passive"))
      (node (ref "R77") (pin "2") (pinfunction "2_2") (pintype "passive"))
      (node (ref "U20") (pin "8") (pinfunction "+VO_8") (pintype "power_in"))
      (node (ref "U21") (pin "4") (pinfunction "VDD_4") (pintype "power_in"))
    )
    (net (code "45") (name "Net-(U21-PROG)") (class "Default")
      (node (ref "R78") (pin "2") (pinfunction "2_2") (pintype "passive"))
      (node (ref "U21") (pin "5") (pinfunction "PROG_5") (pintype "passive"))
    )
    (net (code "46") (name "unconnected-(SW2-Pad3)") (class "Default")
      (node (ref "SW2") (pin "3") (pinfunction "3_3") (pintype "passive"))
    )
  )
)
